# main.net
KiCad netlist of a schematic drawn in EAGLE
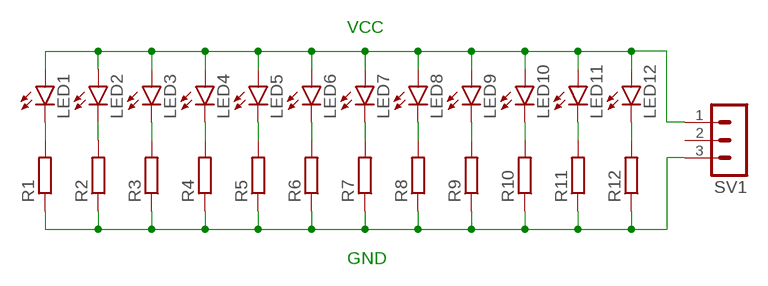
[diagram p0: schematic, sheet 1]

(export (version "E")
  (design (tool "Eeschema 10.0.6"))
  (components
    (comp (ref "LED1")
      (value "LED10MM")
      (footprint "eagle-import:LED10MM")
      (libsource (lib "eagle-import") (part "LED10MM"))
    )
    (comp (ref "LED2")
      (value "LED10MM")
      (footprint "eagle-import:LED10MM")
      (libsource (lib "eagle-import") (part "LED10MM"))
    )
    (comp (ref "LED3")
      (value "LED10MM")
      (footprint "eagle-import:LED10MM")
      (libsource (lib "eagle-import") (part "LED10MM"))
    )
    (comp (ref "LED4")
      (value "LED10MM")
      (footprint "eagle-import:LED10MM")
      (libsource (lib "eagle-import") (part "LED10MM"))
    )
    (comp (ref "LED5")
      (value "LED10MM")
      (footprint "eagle-import:LED10MM")
      (libsource (lib "eagle-import") (part "LED10MM"))
    )
    (comp (ref "LED6")
      (value "LED10MM")
      (footprint "eagle-import:LED10MM")
      (libsource (lib "eagle-import") (part "LED10MM"))
    )
    (comp (ref "LED7")
      (value "LED10MM")
      (footprint "eagle-import:LED10MM")
      (libsource (lib "eagle-import") (part "LED10MM"))
    )
    (comp (ref "LED8")
      (value "LED10MM")
      (footprint "eagle-import:LED10MM")
      (libsource (lib "eagle-import") (part "LED10MM"))
    )
    (comp (ref "LED9")
      (value "LED10MM")
      (footprint "eagle-import:LED10MM")
      (libsource (lib "eagle-import") (part "LED10MM"))
    )
    (comp (ref "LED10")
      (value "LED10MM")
      (footprint "eagle-import:LED10MM")
      (libsource (lib "eagle-import") (part "LED10MM"))
    )
    (comp (ref "LED11")
      (value "LED10MM")
      (footprint "eagle-import:LED10MM")
      (libsource (lib "eagle-import") (part "LED10MM"))
    )
    (comp (ref "LED12")
      (value "LED10MM")
      (footprint "eagle-import:LED10MM")
      (libsource (lib "eagle-import") (part "LED10MM"))
    )
    (comp (ref "R1")
      (value "R-EU_0204/7")
      (footprint "eagle-import:0204_7")
      (libsource (lib "eagle-import") (part "R-EU_0204/7"))
    )
    (comp (ref "R2")
      (value "R-EU_0204/7")
      (footprint "eagle-import:0204_7")
      (libsource (lib "eagle-import") (part "R-EU_0204/7"))
    )
    (comp (ref "R3")
      (value "R-EU_0204/7")
      (footprint "eagle-import:0204_7")
      (libsource (lib "eagle-import") (part "R-EU_0204/7"))
    )
    (comp (ref "R4")
      (value "R-EU_0204/7")
      (footprint "eagle-import:0204_7")
      (libsource (lib "eagle-import") (part "R-EU_0204/7"))
    )
    (comp (ref "R5")
      (value "R-EU_0204/7")
      (footprint "eagle-import:0204_7")
      (libsource (lib "eagle-import") (part "R-EU_0204/7"))
    )
    (comp (ref "R6")
      (value "R-EU_0204/7")
      (footprint "eagle-import:0204_7")
      (libsource (lib "eagle-import") (part "R-EU_0204/7"))
    )
    (comp (ref "R7")
      (value "R-EU_0204/7")
      (footprint "eagle-import:0204_7")
      (libsource (lib "eagle-import") (part "R-EU_0204/7"))
    )
    (comp (ref "R8")
      (value "R-EU_0204/7")
      (footprint "eagle-import:0204_7")
      (libsource (lib "eagle-import") (part "R-EU_0204/7"))
    )
    (comp (ref "R9")
      (value "R-EU_0204/7")
      (footprint "eagle-import:0204_7")
      (libsource (lib "eagle-import") (part "R-EU_0204/7"))
    )
    (comp (ref "R10")
      (value "R-EU_0204/7")
      (footprint "eagle-import:0204_7")
      (libsource (lib "eagle-import") (part "R-EU_0204/7"))
    )
    (comp (ref "R11")
      (value "R-EU_0204/7")
      (footprint "eagle-import:0204_7")
      (libsource (lib "eagle-import") (part "R-EU_0204/7"))
    )
    (comp (ref "R12")
      (value "R-EU_0204/7")
      (footprint "eagle-import:0204_7")
      (libsource (lib "eagle-import") (part "R-EU_0204/7"))
    )
    (comp (ref "SV1")
      (value "MA03-1")
      (footprint "eagle-import:MA03-1")
      (libsource (lib "eagle-import") (part "MA03-1"))
    )
  )
  (nets
    (net (code "1") (name "Net-(LED1-C)") (class "Default")
      (node (ref "LED1") (pin "K") (pinfunction "C_K") (pintype "passive"))
      (node (ref "R1") (pin "2") (pinfunction "2_2") (pintype "passive"))
    )
    (net (code "2") (name "Net-(LED1-PadA)") (class "Default")
      (node (ref "LED1") (pin "A") (pinfunction "A_A") (pintype "passive"))
      (node (ref "LED10") (pin "A") (pinfunction "A_A") (pintype "passive"))
      (node (ref "LED11") (pin "A") (pinfunction "A_A") (pintype "passive"))
      (node (ref "LED12") (pin "A") (pinfunction "A_A") (pintype "passive"))
      (node (ref "LED2") (pin "A") (pinfunction "A_A") (pintype "passive"))
      (node (ref "LED3") (pin "A") (pinfunction "A_A") (pintype "passive"))
      (node (ref "LED4") (pin "A") (pinfunction "A_A") (pintype "passive"))
      (node (ref "LED5") (pin "A") (pinfunction "A_A") (pintype "passive"))
      (node (ref "LED6") (pin "A") (pinfunction "A_A") (pintype "passive"))
      (node (ref "LED7") (pin "A") (pinfunction "A_A") (pintype "passive"))
      (node (ref "LED8") (pin "A") (pinfunction "A_A") (pintype "passive"))
      (node (ref "LED9") (pin "A") (pinfunction "A_A") (pintype "passive"))
      (node (ref "SV1") (pin "1") (pinfunction "1_1") (pintype "passive"))
    )
    (net (code "3") (name "Net-(LED2-C)") (class "Default")
      (node (ref "LED2") (pin "K") (pinfunction "C_K") (pintype "passive"))
      (node (ref "R2") (pin "2") (pinfunction "2_2") (pintype "passive"))
    )
    (net (code "4") (name "Net-(LED3-C)") (class "Default")
      (node (ref "LED3") (pin "K") (pinfunction "C_K") (pintype "passive"))
      (node (ref "R3") (pin "2") (pinfunction "2_2") (pintype "passive"))
    )
    (net (code "5") (name "Net-(LED4-C)") (class "Default")
      (node (ref "LED4") (pin "K") (pinfunction "C_K") (pintype "passive"))
      (node (ref "R4") (pin "2") (pinfunction "2_2") (pintype "passive"))
    )
    (net (code "6") (name "Net-(LED5-C)") (class "Default")
      (node (ref "LED5") (pin "K") (pinfunction "C_K") (pintype "passive"))
      (node (ref "R5") (pin "2") (pinfunction "2_2") (pintype "passive"))
    )
    (net (code "7") (name "Net-(LED6-C)") (class "Default")
      (node (ref "LED6") (pin "K") (pinfunction "C_K") (pintype "passive"))
      (node (ref "R6") (pin "2") (pinfunction "2_2") (pintype "passive"))
    )
    (net (code "8") (name "Net-(LED7-C)") (class "Default")
      (node (ref "LED7") (pin "K") (pinfunction "C_K") (pintype "passive"))
      (node (ref "R7") (pin "2") (pinfunction "2_2") (pintype "passive"))
    )
    (net (code "9") (name "Net-(LED8-C)") (class "Default")
      (node (ref "LED8") (pin "K") (pinfunction "C_K") (pintype "passive"))
      (node (ref "R8") (pin "2") (pinfunction "2_2") (pintype "passive"))
    )
    (net (code "10") (name "Net-(LED9-C)") (class "Default")
      (node (ref "LED9") (pin "K") (pinfunction "C_K") (pintype "passive"))
      (node (ref "R9") (pin "2") (pinfunction "2_2") (pintype "passive"))
    )
    (net (code "11") (name "Net-(LED10-C)") (class "Default")
      (node (ref "LED10") (pin "K") (pinfunction "C_K") (pintype "passive"))
      (node (ref "R10") (pin "2") (pinfunction "2_2") (pintype "passive"))
    )
    (net (code "12") (name "Net-(LED11-C)") (class "Default")
      (node (ref "LED11") (pin "K") (pinfunction "C_K") (pintype "passive"))
      (node (ref "R11") (pin "2") (pinfunction "2_2") (pintype "passive"))
    )
    (net (code "13") (name "Net-(LED12-C)") (class "Default")
      (node (ref "LED12") (pin "K") (pinfunction "C_K") (pintype "passive"))
      (node (ref "R12") (pin "2") (pinfunction "2_2") (pintype "passive"))
    )
    (net (code "14") (name "Net-(R1-Pad1)") (class "Default")
      (node (ref "R1") (pin "1") (pinfunction "1_1") (pintype "passive"))
      (node (ref "R10") (pin "1") (pinfunction "1_1") (pintype "passive"))
      (node (ref "R11") (pin "1") (pinfunction "1_1") (pintype "passive"))
      (node (ref "R12") (pin "1") (pinfunction "1_1") (pintype "passive"))
      (node (ref "R2") (pin "1") (pinfunction "1_1") (pintype "passive"))
      (node (ref "R3") (pin "1") (pinfunction "1_1") (pintype "passive"))
      (node (ref "R4") (pin "1") (pinfunction "1_1") (pintype "passive"))
      (node (ref "R5") (pin "1") (pinfunction "1_1") (pintype "passive"))
      (node (ref "R6") (pin "1") (pinfunction "1_1") (pintype "passive"))
      (node (ref "R7") (pin "1") (pinfunction "1_1") (pintype "passive"))
      (node (ref "R8") (pin "1") (pinfunction "1_1") (pintype "passive"))
      (node (ref "R9") (pin "1") (pinfunction "1_1") (pintype "passive"))
      (node (ref "SV1") (pin "3") (pinfunction "3_3") (pintype "passive"))
    )
    (net (code "15") (name "unconnected-(SV1-Pad2)") (class "Default")
      (node (ref "SV1") (pin "2") (pinfunction "2_2") (pintype "passive"))
    )
  )
)
